# moth_v3_0.net
KiCad netlist of a schematic drawn in EAGLE
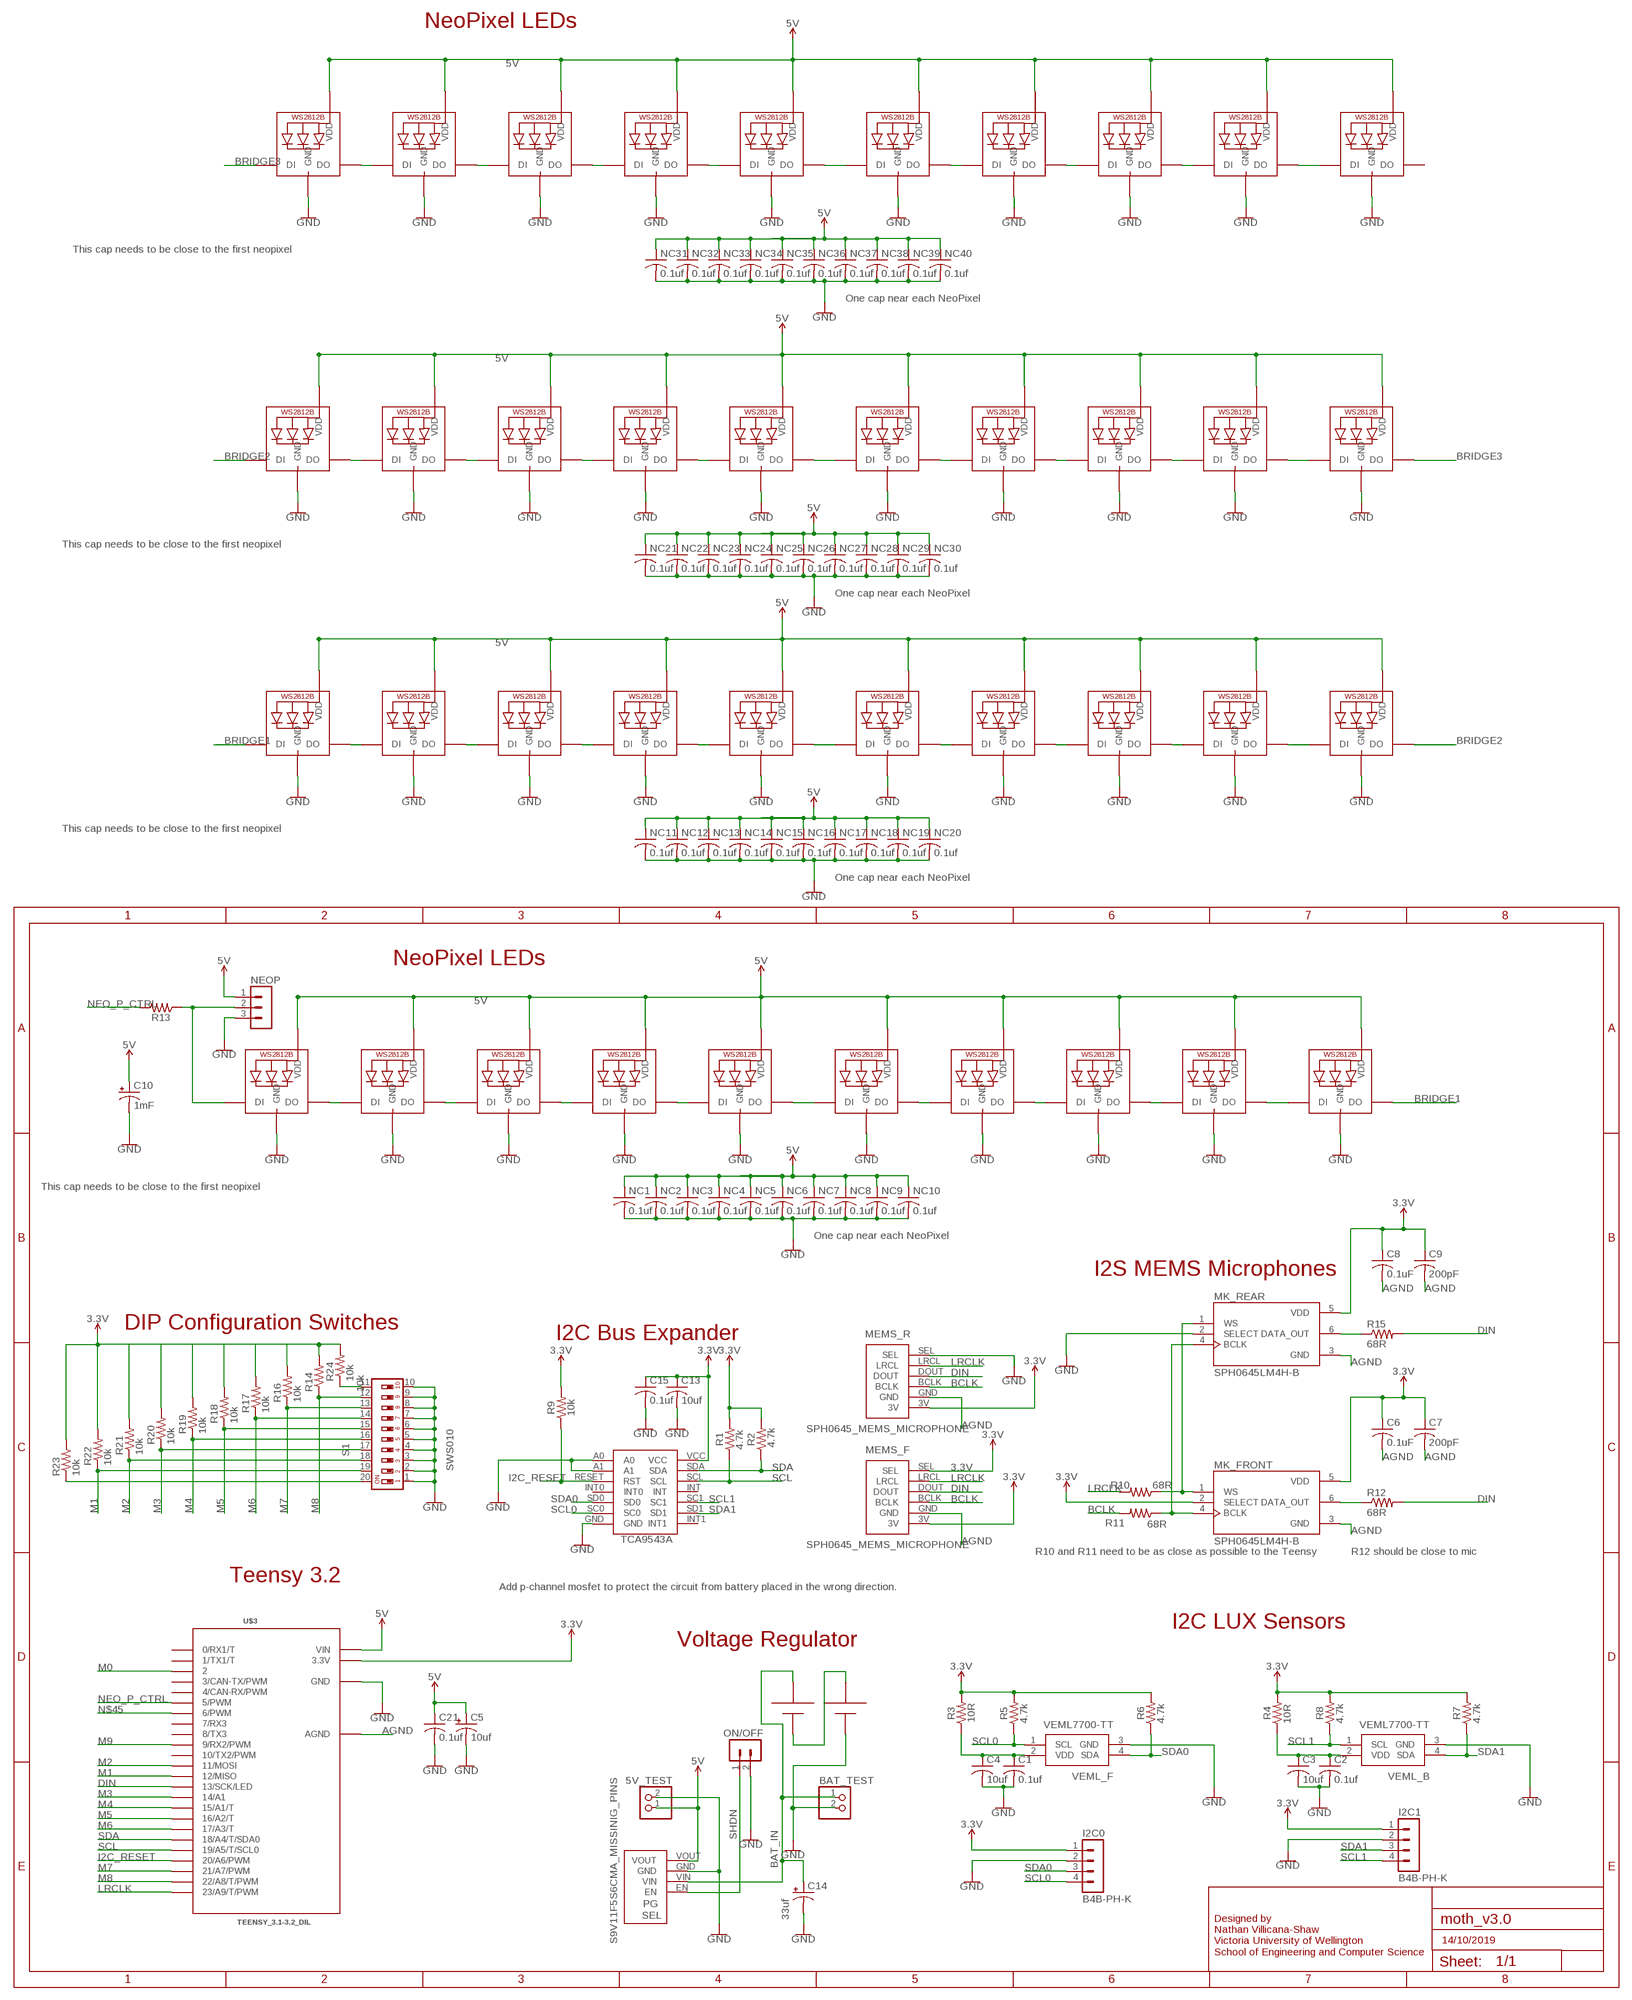
[diagram p0: schematic, sheet 1]

(export (version "E")
  (design (tool "Eeschema 10.0.6"))
  (components
    (comp (ref "5V_TEST")
      (value "PINHD-1X2")
      (footprint "eagle-import:1X02")
      (libsource (lib "eagle-import") (part "PINHD-1X2"))
    )
    (comp (ref "BAT_TEST")
      (value "PINHD-1X2")
      (footprint "eagle-import:1X02")
      (libsource (lib "eagle-import") (part "PINHD-1X2"))
    )
    (comp (ref "C1")
      (value "0.1uf")
      (footprint "eagle-import:C1206K")
      (libsource (lib "eagle-import") (part "C-USC1206K"))
    )
    (comp (ref "C2")
      (value "0.1uf")
      (footprint "eagle-import:C1206K")
      (libsource (lib "eagle-import") (part "C-USC1206K"))
    )
    (comp (ref "C3")
      (value "10uf")
      (footprint "eagle-import:C1206K")
      (libsource (lib "eagle-import") (part "C-USC1206K"))
    )
    (comp (ref "C4")
      (value "10uf")
      (footprint "eagle-import:C1206K")
      (libsource (lib "eagle-import") (part "C-USC1206K"))
    )
    (comp (ref "C5")
      (value "10uf")
      (footprint "eagle-import:E2,5-6")
      (libsource (lib "eagle-import") (part "CPOL-USE2.5-6"))
    )
    (comp (ref "C6")
      (value "0.1uF")
      (footprint "eagle-import:C1206K")
      (libsource (lib "eagle-import") (part "C-USC1206K"))
    )
    (comp (ref "C7")
      (value "200pF")
      (footprint "eagle-import:C1206K")
      (libsource (lib "eagle-import") (part "C-USC1206K"))
    )
    (comp (ref "C8")
      (value "0.1uF")
      (footprint "eagle-import:C1206K")
      (libsource (lib "eagle-import") (part "C-USC1206K"))
    )
    (comp (ref "C9")
      (value "200pF")
      (footprint "eagle-import:C1206K")
      (libsource (lib "eagle-import") (part "C-USC1206K"))
    )
    (comp (ref "C10")
      (value "1mF")
      (footprint "eagle-import:CPOL-RADIAL-5MM-10MM")
      (libsource (lib "eagle-import") (part "1000UF-RADIAL-5MM-25V-20%"))
    )
    (comp (ref "C13")
      (value "10uf")
      (footprint "eagle-import:C1206K")
      (libsource (lib "eagle-import") (part "C-USC1206K"))
    )
    (comp (ref "C14")
      (value "33uf")
      (footprint "eagle-import:E2-5")
      (libsource (lib "eagle-import") (part "CPOL-USE2-5"))
    )
    (comp (ref "C15")
      (value "0.1uf")
      (footprint "eagle-import:C1206K")
      (libsource (lib "eagle-import") (part "C-USC1206K"))
    )
    (comp (ref "C21")
      (value "0.1uf")
      (footprint "eagle-import:C1206K")
      (libsource (lib "eagle-import") (part "C-USC1206K"))
    )
    (comp (ref "I2C0")
      (value "B4B-PH-K")
      (footprint "eagle-import:B4B-PH-K")
      (libsource (lib "eagle-import") (part "B4B-PH-K"))
    )
    (comp (ref "I2C1")
      (value "B4B-PH-K")
      (footprint "eagle-import:B4B-PH-K")
      (libsource (lib "eagle-import") (part "B4B-PH-K"))
    )
    (comp (ref "MEMS_F")
      (value "SPH0645_MEMS_MICROPHONE")
      (footprint "eagle-import:SPH0645")
      (libsource (lib "eagle-import") (part "SPH0645_MEMS_MICROPHONE"))
    )
    (comp (ref "MEMS_R")
      (value "SPH0645_MEMS_MICROPHONE")
      (footprint "eagle-import:SPH0645")
      (libsource (lib "eagle-import") (part "SPH0645_MEMS_MICROPHONE"))
    )
    (comp (ref "MK_FRONT")
      (value "SPH0645LM4H-B")
      (footprint "eagle-import:MIC_SPH0645LM4H-B")
      (fields (field (name "DIGI-KEY_PART_NUMBER") "423-1405-1-ND") (field (name "MF") "Knowles"))
      (libsource (lib "eagle-import") (part "SPH0645LM4H-B"))
    )
    (comp (ref "MK_REAR")
      (value "SPH0645LM4H-B")
      (footprint "eagle-import:MIC_SPH0645LM4H-B")
      (fields (field (name "DIGI-KEY_PART_NUMBER") "423-1405-1-ND") (field (name "MF") "Knowles"))
      (libsource (lib "eagle-import") (part "SPH0645LM4H-B"))
    )
    (comp (ref "NC1")
      (value "0.1uf")
      (footprint "eagle-import:C1206K")
      (libsource (lib "eagle-import") (part "C-USC1206K"))
    )
    (comp (ref "NC2")
      (value "0.1uf")
      (footprint "eagle-import:C1206K")
      (libsource (lib "eagle-import") (part "C-USC1206K"))
    )
    (comp (ref "NC3")
      (value "0.1uf")
      (footprint "eagle-import:C1206K")
      (libsource (lib "eagle-import") (part "C-USC1206K"))
    )
    (comp (ref "NC4")
      (value "0.1uf")
      (footprint "eagle-import:C1206K")
      (libsource (lib "eagle-import") (part "C-USC1206K"))
    )
    (comp (ref "NC5")
      (value "0.1uf")
      (footprint "eagle-import:C1206K")
      (libsource (lib "eagle-import") (part "C-USC1206K"))
    )
    (comp (ref "NC6")
      (value "0.1uf")
      (footprint "eagle-import:C1206K")
      (libsource (lib "eagle-import") (part "C-USC1206K"))
    )
    (comp (ref "NC7")
      (value "0.1uf")
      (footprint "eagle-import:C1206K")
      (libsource (lib "eagle-import") (part "C-USC1206K"))
    )
    (comp (ref "NC8")
      (value "0.1uf")
      (footprint "eagle-import:C1206K")
      (libsource (lib "eagle-import") (part "C-USC1206K"))
    )
    (comp (ref "NC9")
      (value "0.1uf")
      (footprint "eagle-import:C1206K")
      (libsource (lib "eagle-import") (part "C-USC1206K"))
    )
    (comp (ref "NC10")
      (value "0.1uf")
      (footprint "eagle-import:C1206K")
      (libsource (lib "eagle-import") (part "C-USC1206K"))
    )
    (comp (ref "NC11")
      (value "0.1uf")
      (footprint "eagle-import:C1206K")
      (libsource (lib "eagle-import") (part "C-USC1206K"))
    )
    (comp (ref "NC12")
      (value "0.1uf")
      (footprint "eagle-import:C1206K")
      (libsource (lib "eagle-import") (part "C-USC1206K"))
    )
    (comp (ref "NC13")
      (value "0.1uf")
      (footprint "eagle-import:C1206K")
      (libsource (lib "eagle-import") (part "C-USC1206K"))
    )
    (comp (ref "NC14")
      (value "0.1uf")
      (footprint "eagle-import:C1206K")
      (libsource (lib "eagle-import") (part "C-USC1206K"))
    )
    (comp (ref "NC15")
      (value "0.1uf")
      (footprint "eagle-import:C1206K")
      (libsource (lib "eagle-import") (part "C-USC1206K"))
    )
    (comp (ref "NC16")
      (value "0.1uf")
      (footprint "eagle-import:C1206K")
      (libsource (lib "eagle-import") (part "C-USC1206K"))
    )
    (comp (ref "NC17")
      (value "0.1uf")
      (footprint "eagle-import:C1206K")
      (libsource (lib "eagle-import") (part "C-USC1206K"))
    )
    (comp (ref "NC18")
      (value "0.1uf")
      (footprint "eagle-import:C1206K")
      (libsource (lib "eagle-import") (part "C-USC1206K"))
    )
    (comp (ref "NC19")
      (value "0.1uf")
      (footprint "eagle-import:C1206K")
      (libsource (lib "eagle-import") (part "C-USC1206K"))
    )
    (comp (ref "NC20")
      (value "0.1uf")
      (footprint "eagle-import:C1206K")
      (libsource (lib "eagle-import") (part "C-USC1206K"))
    )
    (comp (ref "NC21")
      (value "0.1uf")
      (footprint "eagle-import:C1206K")
      (libsource (lib "eagle-import") (part "C-USC1206K"))
    )
    (comp (ref "NC22")
      (value "0.1uf")
      (footprint "eagle-import:C1206K")
      (libsource (lib "eagle-import") (part "C-USC1206K"))
    )
    (comp (ref "NC23")
      (value "0.1uf")
      (footprint "eagle-import:C1206K")
      (libsource (lib "eagle-import") (part "C-USC1206K"))
    )
    (comp (ref "NC24")
      (value "0.1uf")
      (footprint "eagle-import:C1206K")
      (libsource (lib "eagle-import") (part "C-USC1206K"))
    )
    (comp (ref "NC25")
      (value "0.1uf")
      (footprint "eagle-import:C1206K")
      (libsource (lib "eagle-import") (part "C-USC1206K"))
    )
    (comp (ref "NC26")
      (value "0.1uf")
      (footprint "eagle-import:C1206K")
      (libsource (lib "eagle-import") (part "C-USC1206K"))
    )
    (comp (ref "NC27")
      (value "0.1uf")
      (footprint "eagle-import:C1206K")
      (libsource (lib "eagle-import") (part "C-USC1206K"))
    )
    (comp (ref "NC28")
      (value "0.1uf")
      (footprint "eagle-import:C1206K")
      (libsource (lib "eagle-import") (part "C-USC1206K"))
    )
    (comp (ref "NC29")
      (value "0.1uf")
      (footprint "eagle-import:C1206K")
      (libsource (lib "eagle-import") (part "C-USC1206K"))
    )
    (comp (ref "NC30")
      (value "0.1uf")
      (footprint "eagle-import:C1206K")
      (libsource (lib "eagle-import") (part "C-USC1206K"))
    )
    (comp (ref "NC31")
      (value "0.1uf")
      (footprint "eagle-import:C1206K")
      (libsource (lib "eagle-import") (part "C-USC1206K"))
    )
    (comp (ref "NC32")
      (value "0.1uf")
      (footprint "eagle-import:C1206K")
      (libsource (lib "eagle-import") (part "C-USC1206K"))
    )
    (comp (ref "NC33")
      (value "0.1uf")
      (footprint "eagle-import:C1206K")
      (libsource (lib "eagle-import") (part "C-USC1206K"))
    )
    (comp (ref "NC34")
      (value "0.1uf")
      (footprint "eagle-import:C1206K")
      (libsource (lib "eagle-import") (part "C-USC1206K"))
    )
    (comp (ref "NC35")
      (value "0.1uf")
      (footprint "eagle-import:C1206K")
      (libsource (lib "eagle-import") (part "C-USC1206K"))
    )
    (comp (ref "NC36")
      (value "0.1uf")
      (footprint "eagle-import:C1206K")
      (libsource (lib "eagle-import") (part "C-USC1206K"))
    )
    (comp (ref "NC37")
      (value "0.1uf")
      (footprint "eagle-import:C1206K")
      (libsource (lib "eagle-import") (part "C-USC1206K"))
    )
    (comp (ref "NC38")
      (value "0.1uf")
      (footprint "eagle-import:C1206K")
      (libsource (lib "eagle-import") (part "C-USC1206K"))
    )
    (comp (ref "NC39")
      (value "0.1uf")
      (footprint "eagle-import:C1206K")
      (libsource (lib "eagle-import") (part "C-USC1206K"))
    )
    (comp (ref "NC40")
      (value "0.1uf")
      (footprint "eagle-import:C1206K")
      (libsource (lib "eagle-import") (part "C-USC1206K"))
    )
    (comp (ref "NEO1")
      (value "WS2812B5050")
      (footprint "eagle-import:WS2812B")
      (libsource (lib "eagle-import") (part "WS2812B5050"))
    )
    (comp (ref "NEO2")
      (value "WS2812B5050")
      (footprint "eagle-import:WS2812B")
      (libsource (lib "eagle-import") (part "WS2812B5050"))
    )
    (comp (ref "NEO3")
      (value "WS2812B5050")
      (footprint "eagle-import:WS2812B")
      (libsource (lib "eagle-import") (part "WS2812B5050"))
    )
    (comp (ref "NEO4")
      (value "WS2812B5050")
      (footprint "eagle-import:WS2812B")
      (libsource (lib "eagle-import") (part "WS2812B5050"))
    )
    (comp (ref "NEO5")
      (value "WS2812B5050")
      (footprint "eagle-import:WS2812B")
      (libsource (lib "eagle-import") (part "WS2812B5050"))
    )
    (comp (ref "NEO6")
      (value "WS2812B5050")
      (footprint "eagle-import:WS2812B")
      (libsource (lib "eagle-import") (part "WS2812B5050"))
    )
    (comp (ref "NEO7")
      (value "WS2812B5050")
      (footprint "eagle-import:WS2812B")
      (libsource (lib "eagle-import") (part "WS2812B5050"))
    )
    (comp (ref "NEO8")
      (value "WS2812B5050")
      (footprint "eagle-import:WS2812B")
      (libsource (lib "eagle-import") (part "WS2812B5050"))
    )
    (comp (ref "NEO9")
      (value "WS2812B5050")
      (footprint "eagle-import:WS2812B")
      (libsource (lib "eagle-import") (part "WS2812B5050"))
    )
    (comp (ref "NEO10")
      (value "WS2812B5050")
      (footprint "eagle-import:WS2812B")
      (libsource (lib "eagle-import") (part "WS2812B5050"))
    )
    (comp (ref "NEO11")
      (value "WS2812B5050")
      (footprint "eagle-import:WS2812B")
      (libsource (lib "eagle-import") (part "WS2812B5050"))
    )
    (comp (ref "NEO12")
      (value "WS2812B5050")
      (footprint "eagle-import:WS2812B")
      (libsource (lib "eagle-import") (part "WS2812B5050"))
    )
    (comp (ref "NEO13")
      (value "WS2812B5050")
      (footprint "eagle-import:WS2812B")
      (libsource (lib "eagle-import") (part "WS2812B5050"))
    )
    (comp (ref "NEO14")
      (value "WS2812B5050")
      (footprint "eagle-import:WS2812B")
      (libsource (lib "eagle-import") (part "WS2812B5050"))
    )
    (comp (ref "NEO15")
      (value "WS2812B5050")
      (footprint "eagle-import:WS2812B")
      (libsource (lib "eagle-import") (part "WS2812B5050"))
    )
    (comp (ref "NEO16")
      (value "WS2812B5050")
      (footprint "eagle-import:WS2812B")
      (libsource (lib "eagle-import") (part "WS2812B5050"))
    )
    (comp (ref "NEO17")
      (value "WS2812B5050")
      (footprint "eagle-import:WS2812B")
      (libsource (lib "eagle-import") (part "WS2812B5050"))
    )
    (comp (ref "NEO18")
      (value "WS2812B5050")
      (footprint "eagle-import:WS2812B")
      (libsource (lib "eagle-import") (part "WS2812B5050"))
    )
    (comp (ref "NEO19")
      (value "WS2812B5050")
      (footprint "eagle-import:WS2812B")
      (libsource (lib "eagle-import") (part "WS2812B5050"))
    )
    (comp (ref "NEO20")
      (value "WS2812B5050")
      (footprint "eagle-import:WS2812B")
      (libsource (lib "eagle-import") (part "WS2812B5050"))
    )
    (comp (ref "NEO21")
      (value "WS2812B5050")
      (footprint "eagle-import:WS2812B")
      (libsource (lib "eagle-import") (part "WS2812B5050"))
    )
    (comp (ref "NEO22")
      (value "WS2812B5050")
      (footprint "eagle-import:WS2812B")
      (libsource (lib "eagle-import") (part "WS2812B5050"))
    )
    (comp (ref "NEO23")
      (value "WS2812B5050")
      (footprint "eagle-import:WS2812B")
      (libsource (lib "eagle-import") (part "WS2812B5050"))
    )
    (comp (ref "NEO24")
      (value "WS2812B5050")
      (footprint "eagle-import:WS2812B")
      (libsource (lib "eagle-import") (part "WS2812B5050"))
    )
    (comp (ref "NEO25")
      (value "WS2812B5050")
      (footprint "eagle-import:WS2812B")
      (libsource (lib "eagle-import") (part "WS2812B5050"))
    )
    (comp (ref "NEO26")
      (value "WS2812B5050")
      (footprint "eagle-import:WS2812B")
      (libsource (lib "eagle-import") (part "WS2812B5050"))
    )
    (comp (ref "NEO27")
      (value "WS2812B5050")
      (footprint "eagle-import:WS2812B")
      (libsource (lib "eagle-import") (part "WS2812B5050"))
    )
    (comp (ref "NEO28")
      (value "WS2812B5050")
      (footprint "eagle-import:WS2812B")
      (libsource (lib "eagle-import") (part "WS2812B5050"))
    )
    (comp (ref "NEO29")
      (value "WS2812B5050")
      (footprint "eagle-import:WS2812B")
      (libsource (lib "eagle-import") (part "WS2812B5050"))
    )
    (comp (ref "NEO30")
      (value "WS2812B5050")
      (footprint "eagle-import:WS2812B")
      (libsource (lib "eagle-import") (part "WS2812B5050"))
    )
    (comp (ref "NEO31")
      (value "WS2812B5050")
      (footprint "eagle-import:WS2812B")
      (libsource (lib "eagle-import") (part "WS2812B5050"))
    )
    (comp (ref "NEO32")
      (value "WS2812B5050")
      (footprint "eagle-import:WS2812B")
      (libsource (lib "eagle-import") (part "WS2812B5050"))
    )
    (comp (ref "NEO33")
      (value "WS2812B5050")
      (footprint "eagle-import:WS2812B")
      (libsource (lib "eagle-import") (part "WS2812B5050"))
    )
    (comp (ref "NEO34")
      (value "WS2812B5050")
      (footprint "eagle-import:WS2812B")
      (libsource (lib "eagle-import") (part "WS2812B5050"))
    )
    (comp (ref "NEO35")
      (value "WS2812B5050")
      (footprint "eagle-import:WS2812B")
      (libsource (lib "eagle-import") (part "WS2812B5050"))
    )
    (comp (ref "NEO36")
      (value "WS2812B5050")
      (footprint "eagle-import:WS2812B")
      (libsource (lib "eagle-import") (part "WS2812B5050"))
    )
    (comp (ref "NEO37")
      (value "WS2812B5050")
      (footprint "eagle-import:WS2812B")
      (libsource (lib "eagle-import") (part "WS2812B5050"))
    )
    (comp (ref "NEO38")
      (value "WS2812B5050")
      (footprint "eagle-import:WS2812B")
      (libsource (lib "eagle-import") (part "WS2812B5050"))
    )
    (comp (ref "NEO39")
      (value "WS2812B5050")
      (footprint "eagle-import:WS2812B")
      (libsource (lib "eagle-import") (part "WS2812B5050"))
    )
    (comp (ref "NEO40")
      (value "WS2812B5050")
      (footprint "eagle-import:WS2812B")
      (libsource (lib "eagle-import") (part "WS2812B5050"))
    )
    (comp (ref "NEOP")
      (value "B3B-PH-K")
      (footprint "eagle-import:B3B-PH-K")
      (libsource (lib "eagle-import") (part "B3B-PH-K"))
    )
    (comp (ref "ON/OFF")
      (value "B2B-PH-K")
      (footprint "eagle-import:B2B-PH-K")
      (libsource (lib "eagle-import") (part "B2B-PH-K"))
    )
    (comp (ref "R1")
      (value "4.7k")
      (footprint "eagle-import:R1206W")
      (libsource (lib "eagle-import") (part "R-US_R1206W"))
    )
    (comp (ref "R2")
      (value "4.7k")
      (footprint "eagle-import:R1206W")
      (libsource (lib "eagle-import") (part "R-US_R1206W"))
    )
    (comp (ref "R3")
      (value "10R")
      (footprint "eagle-import:R1206W")
      (libsource (lib "eagle-import") (part "R-US_R1206W"))
    )
    (comp (ref "R4")
      (value "10R")
      (footprint "eagle-import:R1206W")
      (libsource (lib "eagle-import") (part "R-US_R1206W"))
    )
    (comp (ref "R5")
      (value "4.7k")
      (footprint "eagle-import:R1206W")
      (libsource (lib "eagle-import") (part "R-US_R1206W"))
    )
    (comp (ref "R6")
      (value "4.7k")
      (footprint "eagle-import:R1206W")
      (libsource (lib "eagle-import") (part "R-US_R1206W"))
    )
    (comp (ref "R7")
      (value "4.7k")
      (footprint "eagle-import:R1206W")
      (libsource (lib "eagle-import") (part "R-US_R1206W"))
    )
    (comp (ref "R8")
      (value "4.7k")
      (footprint "eagle-import:R1206W")
      (libsource (lib "eagle-import") (part "R-US_R1206W"))
    )
    (comp (ref "R9")
      (value "10k")
      (footprint "eagle-import:R1206W")
      (libsource (lib "eagle-import") (part "R-US_R1206W"))
    )
    (comp (ref "R10")
      (value "68R")
      (footprint "eagle-import:M1206")
      (libsource (lib "eagle-import") (part "R-US_M1206"))
    )
    (comp (ref "R11")
      (value "68R")
      (footprint "eagle-import:M1206")
      (libsource (lib "eagle-import") (part "R-US_M1206"))
    )
    (comp (ref "R12")
      (value "68R")
      (footprint "eagle-import:M1206")
      (libsource (lib "eagle-import") (part "R-US_M1206"))
    )
    (comp (ref "R13")
      (value "300 R")
      (footprint "eagle-import:R1206W")
      (libsource (lib "eagle-import") (part "R-US_R1206W"))
    )
    (comp (ref "R14")
      (value "10k")
      (footprint "eagle-import:R1206W")
      (libsource (lib "eagle-import") (part "R-US_R1206W"))
    )
    (comp (ref "R15")
      (value "68R")
      (footprint "eagle-import:M1206")
      (libsource (lib "eagle-import") (part "R-US_M1206"))
    )
    (comp (ref "R16")
      (value "10k")
      (footprint "eagle-import:R1206W")
      (libsource (lib "eagle-import") (part "R-US_R1206W"))
    )
    (comp (ref "R17")
      (value "10k")
      (footprint "eagle-import:R1206W")
      (libsource (lib "eagle-import") (part "R-US_R1206W"))
    )
    (comp (ref "R18")
      (value "10k")
      (footprint "eagle-import:R1206W")
      (libsource (lib "eagle-import") (part "R-US_R1206W"))
    )
    (comp (ref "R19")
      (value "10k")
      (footprint "eagle-import:R1206W")
      (libsource (lib "eagle-import") (part "R-US_R1206W"))
    )
    (comp (ref "R20")
      (value "10k")
      (footprint "eagle-import:R1206W")
      (libsource (lib "eagle-import") (part "R-US_R1206W"))
    )
    (comp (ref "R21")
      (value "10k")
      (footprint "eagle-import:R1206W")
      (libsource (lib "eagle-import") (part "R-US_R1206W"))
    )
    (comp (ref "R22")
      (value "10k")
      (footprint "eagle-import:R1206W")
      (libsource (lib "eagle-import") (part "R-US_R1206W"))
    )
    (comp (ref "R23")
      (value "10k")
      (footprint "eagle-import:R1206W")
      (libsource (lib "eagle-import") (part "R-US_R1206W"))
    )
    (comp (ref "R24")
      (value "10k")
      (footprint "eagle-import:R1206W")
      (libsource (lib "eagle-import") (part "R-US_R1206W"))
    )
    (comp (ref "S1")
      (value "SWS010")
      (footprint "eagle-import:SMS-010")
      (libsource (lib "eagle-import") (part "SWS010"))
    )
    (comp (ref "U$1")
      (value "TCA9543A")
      (footprint "eagle-import:SO14")
      (libsource (lib "eagle-import") (part "TCA9543A"))
    )
    (comp (ref "U$2")
      (value "BK-18650-PC4")
      (footprint "eagle-import:18650-PC4")
      (fields (field (name "MF") "MPD"))
      (libsource (lib "eagle-import") (part "BK-18650-PC4"))
    )
    (comp (ref "U$3")
      (value "TEENSY_3.1-3.2_DIL")
      (footprint "eagle-import:TEENSY_3.0-3.2&LC_DIL")
      (libsource (lib "eagle-import") (part "TEENSY_3.1-3.2_DIL"))
    )
    (comp (ref "U$6")
      (value "S9V11F5S6CMA_MISSINIG_PINS")
      (footprint "eagle-import:S9V11F3S5CMA_MISSING_PINS")
      (libsource (lib "eagle-import") (part "S9V11F5S6CMA_MISSINIG_PINS"))
    )
    (comp (ref "VEML_B")
      (value "VEML7700-TT")
      (footprint "eagle-import:VEML7700")
      (fields (field (name "MOUSER_PART_NUMBER") "78-VEML7700-TT") (field (name "RS_PART_NUMBER") "1226791P"))
      (libsource (lib "eagle-import") (part "VEML7700-TT"))
    )
    (comp (ref "VEML_F")
      (value "VEML7700-TT")
      (footprint "eagle-import:VEML7700")
      (fields (field (name "MOUSER_PART_NUMBER") "78-VEML7700-TT") (field (name "RS_PART_NUMBER") "1226791P"))
      (libsource (lib "eagle-import") (part "VEML7700-TT"))
    )
  )
  (nets
    (net (code "1") (name "/AGND") (class "Default")
      (node (ref "C6") (pin "2") (pinfunction "2_2") (pintype "passive"))
      (node (ref "C7") (pin "2") (pinfunction "2_2") (pintype "passive"))
      (node (ref "C8") (pin "2") (pinfunction "2_2") (pintype "passive"))
      (node (ref "C9") (pin "2") (pinfunction "2_2") (pintype "passive"))
      (node (ref "MEMS_F") (pin "GND") (pinfunction "GND_GND") (pintype "bidirectional"))
      (node (ref "MEMS_R") (pin "GND") (pinfunction "GND_GND") (pintype "bidirectional"))
      (node (ref "MK_FRONT") (pin "3") (pinfunction "GND_3") (pintype "power_in"))
      (node (ref "MK_REAR") (pin "3") (pinfunction "GND_3") (pintype "power_in"))
      (node (ref "U$3") (pin "AGND") (pinfunction "AGND_AGND") (pintype "power_in"))
    )
    (net (code "2") (name "/BAT_IN") (class "Default")
      (node (ref "BAT_TEST") (pin "1") (pinfunction "1_1") (pintype "passive"))
      (node (ref "C14") (pin "+") (pinfunction "+_+") (pintype "passive"))
      (node (ref "U$2") (pin "+1") (pinfunction "+1_+1") (pintype "bidirectional"))
      (node (ref "U$6") (pin "VIN") (pinfunction "VIN_VIN") (pintype "bidirectional"))
    )
    (net (code "3") (name "/BCLK") (class "Default")
      (node (ref "MEMS_F") (pin "BCLK") (pinfunction "BCLK_BCLK") (pintype "bidirectional"))
      (node (ref "MEMS_R") (pin "BCLK") (pinfunction "BCLK_BCLK") (pintype "bidirectional"))
      (node (ref "R11") (pin "2") (pinfunction "2_2") (pintype "passive"))
    )
    (net (code "4") (name "/BRIDGE1") (class "Default")
      (node (ref "NEO10") (pin "2-DOUT") (pinfunction "DO_2-DOUT") (pintype "output"))
      (node (ref "NEO14") (pin "4-DIN") (pinfunction "DI_4-DIN") (pintype "input"))
    )
    (net (code "5") (name "/BRIDGE2") (class "Default")
      (node (ref "NEO20") (pin "2-DOUT") (pinfunction "DO_2-DOUT") (pintype "output"))
      (node (ref "NEO24") (pin "4-DIN") (pinfunction "DI_4-DIN") (pintype "input"))
    )
    (net (code "6") (name "/BRIDGE3") (class "Default")
      (node (ref "NEO30") (pin "2-DOUT") (pinfunction "DO_2-DOUT") (pintype "output"))
      (node (ref "NEO34") (pin "4-DIN") (pinfunction "DI_4-DIN") (pintype "input"))
    )
    (net (code "7") (name "/DIN") (class "Default")
      (node (ref "MEMS_F") (pin "DOUT") (pinfunction "DOUT_DOUT") (pintype "bidirectional"))
      (node (ref "MEMS_R") (pin "DOUT") (pinfunction "DOUT_DOUT") (pintype "bidirectional"))
      (node (ref "R12") (pin "2") (pinfunction "2_2") (pintype "passive"))
      (node (ref "R15") (pin "2") (pinfunction "2_2") (pintype "passive"))
      (node (ref "U$3") (pin "13") (pinfunction "13/SCK/LED_13") (pintype "bidirectional"))
    )
    (net (code "8") (name "/I2C_RESET") (class "Default")
      (node (ref "R9") (pin "1") (pinfunction "1_1") (pintype "passive"))
      (node (ref "U$1") (pin "RESET") (pinfunction "RST_RESET") (pintype "bidirectional"))
      (node (ref "U$3") (pin "20/A6") (pinfunction "20/A6/PWM_20/A6") (pintype "bidirectional"))
    )
    (net (code "9") (name "/LRCLK") (class "Default")
      (node (ref "MEMS_F") (pin "LRCL") (pinfunction "LRCL_LRCL") (pintype "bidirectional"))
      (node (ref "MEMS_R") (pin "LRCL") (pinfunction "LRCL_LRCL") (pintype "bidirectional"))
      (node (ref "R10") (pin "2") (pinfunction "2_2") (pintype "passive"))
      (node (ref "U$3") (pin "23/A9") (pinfunction "23/A9/T/PWM_23/A9") (pintype "bidirectional"))
    )
    (net (code "10") (name "/M0") (class "Default")
      (node (ref "U$3") (pin "2") (pinfunction "2_2") (pintype "bidirectional"))
    )
    (net (code "11") (name "/M1") (class "Default")
      (node (ref "R22") (pin "1") (pinfunction "1_1") (pintype "passive"))
      (node (ref "S1") (pin "19") (pinfunction "19_19") (pintype "passive"))
      (node (ref "U$3") (pin "12") (pinfunction "12/MISO_12") (pintype "bidirectional"))
    )
    (net (code "12") (name "/M2") (class "Default")
      (node (ref "R21") (pin "1") (pinfunction "1_1") (pintype "passive"))
      (node (ref "S1") (pin "18") (pinfunction "18_18") (pintype "passive"))
      (node (ref "U$3") (pin "11") (pinfunction "11/MOSI_11") (pintype "bidirectional"))
    )
    (net (code "13") (name "/M3") (class "Default")
      (node (ref "R20") (pin "1") (pinfunction "1_1") (pintype "passive"))
      (node (ref "S1") (pin "17") (pinfunction "17_17") (pintype "passive"))
      (node (ref "U$3") (pin "14/A0") (pinfunction "14/A1_14/A0") (pintype "bidirectional"))
    )
    (net (code "14") (name "/M4") (class "Default")
      (node (ref "R19") (pin "1") (pinfunction "1_1") (pintype "passive"))
      (node (ref "S1") (pin "16") (pinfunction "16_16") (pintype "passive"))
      (node (ref "U$3") (pin "15/A1") (pinfunction "15/A1/T_15/A1") (pintype "bidirectional"))
    )
    (net (code "15") (name "/M5") (class "Default")
      (node (ref "R18") (pin "1") (pinfunction "1_1") (pintype "passive"))
      (node (ref "S1") (pin "15") (pinfunction "15_15") (pintype "passive"))
      (node (ref "U$3") (pin "16/A2") (pinfunction "16/A2/T_16/A2") (pintype "bidirectional"))
    )
    (net (code "16") (name "/M6") (class "Default")
      (node (ref "R17") (pin "1") (pinfunction "1_1") (pintype "passive"))
      (node (ref "S1") (pin "14") (pinfunction "14_14") (pintype "passive"))
      (node (ref "U$3") (pin "17/A3") (pinfunction "17/A3/T_17/A3") (pintype "bidirectional"))
    )
    (net (code "17") (name "/M7") (class "Default")
      (node (ref "R16") (pin "1") (pinfunction "1_1") (pintype "passive"))
      (node (ref "S1") (pin "13") (pinfunction "13_13") (pintype "passive"))
      (node (ref "U$3") (pin "21/A7") (pinfunction "21/A7/PWM_21/A7") (pintype "bidirectional"))
    )
    (net (code "18") (name "/M8") (class "Default")
      (node (ref "R14") (pin "1") (pinfunction "1_1") (pintype "passive"))
      (node (ref "S1") (pin "12") (pinfunction "12_12") (pintype "passive"))
      (node (ref "U$3") (pin "22/A8") (pinfunction "22/A8/T/PWM_22/A8") (pintype "bidirectional"))
    )
    (net (code "19") (name "/M9") (class "Default")
      (node (ref "U$3") (pin "9") (pinfunction "9/RX2/PWM_9") (pintype "bidirectional"))
    )
    (net (code "20") (name "/N$45") (class "Default")
      (node (ref "U$3") (pin "6") (pinfunction "6/PWM_6") (pintype "bidirectional"))
    )
    (net (code "21") (name "/NEO_P_CTRL") (class "Default")
      (node (ref "R13") (pin "2") (pinfunction "2_2") (pintype "passive"))
      (node (ref "U$3") (pin "5") (pinfunction "5/PWM_5") (pintype "bidirectional"))
    )
    (net (code "22") (name "/SCL") (class "Default")
      (node (ref "R1") (pin "1") (pinfunction "1_1") (pintype "passive"))
      (node (ref "U$1") (pin "SCL") (pinfunction "SCL_SCL") (pintype "bidirectional"))
      (node (ref "U$3") (pin "19/A5") (pinfunction "19/A5/T/SCL0_19/A5") (pintype "bidirectional"))
    )
    (net (code "23") (name "/SCL0") (class "Default")
      (node (ref "I2C0") (pin "4") (pinfunction "4_4") (pintype "passive"))
      (node (ref "R5") (pin "1") (pinfunction "1_1") (pintype "passive"))
      (node (ref "U$1") (pin "SC0") (pinfunction "SC0_SC0") (pintype "bidirectional"))
      (node (ref "VEML_F") (pin "1") (pinfunction "SCL_1") (pintype "bidirectional"))
    )
    (net (code "24") (name "/SCL1") (class "Default")
      (node (ref "I2C1") (pin "4") (pinfunction "4_4") (pintype "passive"))
      (node (ref "R8") (pin "1") (pinfunction "1_1") (pintype "passive"))
      (node (ref "U$1") (pin "SC1") (pinfunction "SC1_SC1") (pintype "bidirectional"))
      (node (ref "VEML_B") (pin "1") (pinfunction "SCL_1") (pintype "bidirectional"))
    )
    (net (code "25") (name "/SDA") (class "Default")
      (node (ref "R2") (pin "1") (pinfunction "1_1") (pintype "passive"))
      (node (ref "U$1") (pin "SDA") (pinfunction "SDA_SDA") (pintype "bidirectional"))
      (node (ref "U$3") (pin "18/A4") (pinfunction "18/A4/T/SDA0_18/A4") (pintype "bidirectional"))
    )
    (net (code "26") (name "/SDA0") (class "Default")
      (node (ref "I2C0") (pin "3") (pinfunction "3_3") (pintype "passive"))
      (node (ref "R6") (pin "1") (pinfunction "1_1") (pintype "passive"))
      (node (ref "U$1") (pin "SD0") (pinfunction "SD0_SD0") (pintype "bidirectional"))
      (node (ref "VEML_F") (pin "4") (pinfunction "SDA_4") (pintype "bidirectional"))
    )
    (net (code "27") (name "/SDA1") (class "Default")
      (node (ref "I2C1") (pin "3") (pinfunction "3_3") (pintype "passive"))
      (node (ref "R7") (pin "1") (pinfunction "1_1") (pintype "passive"))
      (node (ref "U$1") (pin "SD1") (pinfunction "SD1_SD1") (pintype "bidirectional"))
      (node (ref "VEML_B") (pin "4") (pinfunction "SDA_4") (pintype "bidirectional"))
    )
    (net (code "28") (name "/SHDN") (class "Default")
      (node (ref "ON/OFF") (pin "1") (pinfunction "1_1") (pintype "passive"))
      (node (ref "U$6") (pin "EN") (pinfunction "EN_EN") (pintype "bidirectional"))
    )
    (net (code "29") (name "3.3V") (class "Default")
      (node (ref "C13") (pin "1") (pinfunction "1_1") (pintype "passive"))
      (node (ref "C15") (pin "1") (pinfunction "1_1") (pintype "passive"))
      (node (ref "C6") (pin "1") (pinfunction "1_1") (pintype "passive"))
      (node (ref "C7") (pin "1") (pinfunction "1_1") (pintype "passive"))
      (node (ref "C8") (pin "1") (pinfunction "1_1") (pintype "passive"))
      (node (ref "C9") (pin "1") (pinfunction "1_1") (pintype "passive"))
      (node (ref "I2C0") (pin "1") (pinfunction "1_1") (pintype "passive"))
      (node (ref "I2C1") (pin "1") (pinfunction "1_1") (pintype "passive"))
      (node (ref "MEMS_F") (pin "3V") (pinfunction "3V_3V") (pintype "bidirectional"))
      (node (ref "MEMS_F") (pin "SEL") (pinfunction "SEL_SEL") (pintype "bidirectional"))
      (node (ref "MEMS_R") (pin "3V") (pinfunction "3V_3V") (pintype "bidirectional"))
      (node (ref "MK_FRONT") (pin "2") (pinfunction "SELECT_2") (pintype "input"))
      (node (ref "MK_FRONT") (pin "5") (pinfunction "VDD_5") (pintype "power_in"))
      (node (ref "MK_REAR") (pin "5") (pinfunction "VDD_5") (pintype "power_in"))
      (node (ref "R1") (pin "2") (pinfunction "2_2") (pintype "passive"))
      (node (ref "R14") (pin "2") (pinfunction "2_2") (pintype "passive"))
      (node (ref "R2") (pin "2") (pinfunction "2_2") (pintype "passive"))
      (node (ref "R22") (pin "2") (pinfunction "2_2") (pintype "passive"))
      (node (ref "R23") (pin "2") (pinfunction "2_2") (pintype "passive"))
      (node (ref "R24") (pin "2") (pinfunction "2_2") (pintype "passive"))
      (node (ref "R3") (pin "2") (pinfunction "2_2") (pintype "passive"))
      (node (ref "R4") (pin "2") (pinfunction "2_2") (pintype "passive"))
      (node (ref "R5") (pin "2") (pinfunction "2_2") (pintype "passive"))
      (node (ref "R6") (pin "2") (pinfunction "2_2") (pintype "passive"))
      (node (ref "R7") (pin "2") (pinfunction "2_2") (pintype "passive"))
      (node (ref "R8") (pin "2") (pinfunction "2_2") (pintype "passive"))
      (node (ref "R9") (pin "2") (pinfunction "2_2") (pintype "passive"))
      (node (ref "U$1") (pin "VCC") (pinfunction "VCC_VCC") (pintype "bidirectional"))
      (node (ref "U$3") (pin "3.3V") (pinfunction "3.3V_3.3V") (pintype "power_in"))
    )
    (net (code "30") (name "5V") (class "Default")
      (node (ref "5V_TEST") (pin "1") (pinfunction "1_1") (pintype "passive"))
      (node (ref "C10") (pin "+") (pinfunction "+_+") (pintype "passive"))
      (node (ref "C21") (pin "1") (pinfunction "1_1") (pintype "passive"))
      (node (ref "C5") (pin "+") (pinfunction "+_+") (pintype "passive"))
      (node (ref "NC1") (pin "1") (pinfunction "1_1") (pintype "passive"))
      (node (ref "NC10") (pin "1") (pinfunction "1_1") (pintype "passive"))
      (node (ref "NC11") (pin "1") (pinfunction "1_1") (pintype "passive"))
      (node (ref "NC12") (pin "1") (pinfunction "1_1") (pintype "passive"))
      (node (ref "NC13") (pin "1") (pinfunction "1_1") (pintype "passive"))
      (node (ref "NC14") (pin "1") (pinfunction "1_1") (pintype "passive"))
      (node (ref "NC15") (pin "1") (pinfunction "1_1") (pintype "passive"))
      (node (ref "NC16") (pin "1") (pinfunction "1_1") (pintype "passive"))
      (node (ref "NC17") (pin "1") (pinfunction "1_1") (pintype "passive"))
      (node (ref "NC18") (pin "1") (pinfunction "1_1") (pintype "passive"))
      (node (ref "NC19") (pin "1") (pinfunction "1_1") (pintype "passive"))
      (node (ref "NC2") (pin "1") (pinfunction "1_1") (pintype "passive"))
      (node (ref "NC20") (pin "1") (pinfunction "1_1") (pintype "passive"))
      (node (ref "NC21") (pin "1") (pinfunction "1_1") (pintype "passive"))
      (node (ref "NC22") (pin "1") (pinfunction "1_1") (pintype "passive"))
      (node (ref "NC23") (pin "1") (pinfunction "1_1") (pintype "passive"))
      (node (ref "NC24") (pin "1") (pinfunction "1_1") (pintype "passive"))
      (node (ref "NC25") (pin "1") (pinfunction "1_1") (pintype "passive"))
      (node (ref "NC26") (pin "1") (pinfunction "1_1") (pintype "passive"))
      (node (ref "NC27") (pin "1") (pinfunction "1_1") (pintype "passive"))
      (node (ref "NC28") (pin "1") (pinfunction "1_1") (pintype "passive"))
      (node (ref "NC29") (pin "1") (pinfunction "1_1") (pintype "passive"))
      (node (ref "NC3") (pin "1") (pinfunction "1_1") (pintype "passive"))
      (node (ref "NC30") (pin "1") (pinfunction "1_1") (pintype "passive"))
      (node (ref "NC31") (pin "1") (pinfunction "1_1") (pintype "passive"))
      (node (ref "NC32") (pin "1") (pinfunction "1_1") (pintype "passive"))
      (node (ref "NC33") (pin "1") (pinfunction "1_1") (pintype "passive"))
      (node (ref "NC34") (pin "1") (pinfunction "1_1") (pintype "passive"))
      (node (ref "NC35") (pin "1") (pinfunction "1_1") (pintype "passive"))
      (node (ref "NC36") (pin "1") (pinfunction "1_1") (pintype "passive"))
      (node (ref "NC37") (pin "1") (pinfunction "1_1") (pintype "passive"))
      (node (ref "NC38") (pin "1") (pinfunction "1_1") (pintype "passive"))
      (node (ref "NC39") (pin "1") (pinfunction "1_1") (pintype "passive"))
      (node (ref "NC4") (pin "1") (pinfunction "1_1") (pintype "passive"))
      (node (ref "NC40") (pin "1") (pinfunction "1_1") (pintype "passive"))
      (node (ref "NC5") (pin "1") (pinfunction "1_1") (pintype "passive"))
      (node (ref "NC6") (pin "1") (pinfunction "1_1") (pintype "passive"))
      (node (ref "NC7") (pin "1") (pinfunction "1_1") (pintype "passive"))
      (node (ref "NC8") (pin "1") (pinfunction "1_1") (pintype "passive"))
      (node (ref "NC9") (pin "1") (pinfunction "1_1") (pintype "passive"))
      (node (ref "NEO1") (pin "1-VDD") (pinfunction "VDD_1-VDD") (pintype "power_in"))
      (node (ref "NEO10") (pin "1-VDD") (pinfunction "VDD_1-VDD") (pintype "power_in"))
      (node (ref "NEO11") (pin "1-VDD") (pinfunction "VDD_1-VDD") (pintype "power_in"))
      (node (ref "NEO12") (pin "1-VDD") (pinfunction "VDD_1-VDD") (pintype "power_in"))
      (node (ref "NEO13") (pin "1-VDD") (pinfunction "VDD_1-VDD") (pintype "power_in"))
      (node (ref "NEO14") (pin "1-VDD") (pinfunction "VDD_1-VDD") (pintype "power_in"))
      (node (ref "NEO15") (pin "1-VDD") (pinfunction "VDD_1-VDD") (pintype "power_in"))
      (node (ref "NEO16") (pin "1-VDD") (pinfunction "VDD_1-VDD") (pintype "power_in"))
      (node (ref "NEO17") (pin "1-VDD") (pinfunction "VDD_1-VDD") (pintype "power_in"))
      (node (ref "NEO18") (pin "1-VDD") (pinfunction "VDD_1-VDD") (pintype "power_in"))
      (node (ref "NEO19") (pin "1-VDD") (pinfunction "VDD_1-VDD") (pintype "power_in"))
      (node (ref "NEO2") (pin "1-VDD") (pinfunction "VDD_1-VDD") (pintype "power_in"))
      (node (ref "NEO20") (pin "1-VDD") (pinfunction "VDD_1-VDD") (pintype "power_in"))
      (node (ref "NEO21") (pin "1-VDD") (pinfunction "VDD_1-VDD") (pintype "power_in"))
      (node (ref "NEO22") (pin "1-VDD") (pinfunction "VDD_1-VDD") (pintype "power_in"))
      (node (ref "NEO23") (pin "1-VDD") (pinfunction "VDD_1-VDD") (pintype "power_in"))
      (node (ref "NEO24") (pin "1-VDD") (pinfunction "VDD_1-VDD") (pintype "power_in"))
      (node (ref "NEO25") (pin "1-VDD") (pinfunction "VDD_1-VDD") (pintype "power_in"))
      (node (ref "NEO26") (pin "1-VDD") (pinfunction "VDD_1-VDD") (pintype "power_in"))
      (node (ref "NEO27") (pin "1-VDD") (pinfunction "VDD_1-VDD") (pintype "power_in"))
      (node (ref "NEO28") (pin "1-VDD") (pinfunction "VDD_1-VDD") (pintype "power_in"))
      (node (ref "NEO29") (pin "1-VDD") (pinfunction "VDD_1-VDD") (pintype "power_in"))
      (node (ref "NEO3") (pin "1-VDD") (pinfunction "VDD_1-VDD") (pintype "power_in"))
      (node (ref "NEO30") (pin "1-VDD") (pinfunction "VDD_1-VDD") (pintype "power_in"))
      (node (ref "NEO31") (pin "1-VDD") (pinfunction "VDD_1-VDD") (pintype "power_in"))
      (node (ref "NEO32") (pin "1-VDD") (pinfunction "VDD_1-VDD") (pintype "power_in"))
      (node (ref "NEO33") (pin "1-VDD") (pinfunction "VDD_1-VDD") (pintype "power_in"))
      (node (ref "NEO34") (pin "1-VDD") (pinfunction "VDD_1-VDD") (pintype "power_in"))
      (node (ref "NEO35") (pin "1-VDD") (pinfunction "VDD_1-VDD") (pintype "power_in"))
      (node (ref "NEO36") (pin "1-VDD") (pinfunction "VDD_1-VDD") (pintype "power_in"))
      (node (ref "NEO37") (pin "1-VDD") (pinfunction "VDD_1-VDD") (pintype "power_in"))
      (node (ref "NEO38") (pin "1-VDD") (pinfunction "VDD_1-VDD") (pintype "power_in"))
      (node (ref "NEO39") (pin "1-VDD") (pinfunction "VDD_1-VDD") (pintype "power_in"))
      (node (ref "NEO4") (pin "1-VDD") (pinfunction "VDD_1-VDD") (pintype "power_in"))
      (node (ref "NEO40") (pin "1-VDD") (pinfunction "VDD_1-VDD") (pintype "power_in"))
      (node (ref "NEO5") (pin "1-VDD") (pinfunction "VDD_1-VDD") (pintype "power_in"))
      (node (ref "NEO6") (pin "1-VDD") (pinfunction "VDD_1-VDD") (pintype "power_in"))
      (node (ref "NEO7") (pin "1-VDD") (pinfunction "VDD_1-VDD") (pintype "power_in"))
      (node (ref "NEO8") (pin "1-VDD") (pinfunction "VDD_1-VDD") (pintype "power_in"))
      (node (ref "NEO9") (pin "1-VDD") (pinfunction "VDD_1-VDD") (pintype "power_in"))
      (node (ref "NEOP") (pin "1") (pinfunction "1_1") (pintype "passive"))
      (node (ref "U$3") (pin "VIN") (pinfunction "VIN_VIN") (pintype "power_in"))
      (node (ref "U$6") (pin "VOUT") (pinfunction "VOUT_VOUT") (pintype "bidirectional"))
    )
    (net (code "31") (name "GND") (class "Default")
      (node (ref "5V_TEST") (pin "2") (pinfunction "2_2") (pintype "passive"))
      (node (ref "BAT_TEST") (pin "2") (pinfunction "2_2") (pintype "passive"))
      (node (ref "C1") (pin "2") (pinfunction "2_2") (pintype "passive"))
      (node (ref "C10") (pin "-") (pinfunction "-_-") (pintype "passive"))
      (node (ref "C13") (pin "2") (pinfunction "2_2") (pintype "passive"))
      (node (ref "C14") (pin "-") (pinfunction "-_-") (pintype "passive"))
      (node (ref "C15") (pin "2") (pinfunction "2_2") (pintype "passive"))
      (node (ref "C2") (pin "2") (pinfunction "2_2") (pintype "passive"))
      (node (ref "C21") (pin "2") (pinfunction "2_2") (pintype "passive"))
      (node (ref "C3") (pin "2") (pinfunction "2_2") (pintype "passive"))
      (node (ref "C4") (pin "2") (pinfunction "2_2") (pintype "passive"))
      (node (ref "C5") (pin "-") (pinfunction "-_-") (pintype "passive"))
      (node (ref "I2C0") (pin "2") (pinfunction "2_2") (pintype "passive"))
      (node (ref "I2C1") (pin "2") (pinfunction "2_2") (pintype "passive"))
      (node (ref "MEMS_R") (pin "SEL") (pinfunction "SEL_SEL") (pintype "bidirectional"))
      (node (ref "MK_REAR") (pin "2") (pinfunction "SELECT_2") (pintype "input"))
      (node (ref "NC1") (pin "2") (pinfunction "2_2") (pintype "passive"))
      (node (ref "NC10") (pin "2") (pinfunction "2_2") (pintype "passive"))
      (node (ref "NC11") (pin "2") (pinfunction "2_2") (pintype "passive"))
      (node (ref "NC12") (pin "2") (pinfunction "2_2") (pintype "passive"))
      (node (ref "NC13") (pin "2") (pinfunction "2_2") (pintype "passive"))
      (node (ref "NC14") (pin "2") (pinfunction "2_2") (pintype "passive"))
      (node (ref "NC15") (pin "2") (pinfunction "2_2") (pintype "passive"))
      (node (ref "NC16") (pin "2") (pinfunction "2_2") (pintype "passive"))
      (node (ref "NC17") (pin "2") (pinfunction "2_2") (pintype "passive"))
      (node (ref "NC18") (pin "2") (pinfunction "2_2") (pintype "passive"))
      (node (ref "NC19") (pin "2") (pinfunction "2_2") (pintype "passive"))
      (node (ref "NC2") (pin "2") (pinfunction "2_2") (pintype "passive"))
      (node (ref "NC20") (pin "2") (pinfunction "2_2") (pintype "passive"))
      (node (ref "NC21") (pin "2") (pinfunction "2_2") (pintype "passive"))
      (node (ref "NC22") (pin "2") (pinfunction "2_2") (pintype "passive"))
      (node (ref "NC23") (pin "2") (pinfunction "2_2") (pintype "passive"))
      (node (ref "NC24") (pin "2") (pinfunction "2_2") (pintype "passive"))
      (node (ref "NC25") (pin "2") (pinfunction "2_2") (pintype "passive"))
      (node (ref "NC26") (pin "2") (pinfunction "2_2") (pintype "passive"))
      (node (ref "NC27") (pin "2") (pinfunction "2_2") (pintype "passive"))
      (node (ref "NC28") (pin "2") (pinfunction "2_2") (pintype "passive"))
      (node (ref "NC29") (pin "2") (pinfunction "2_2") (pintype "passive"))
      (node (ref "NC3") (pin "2") (pinfunction "2_2") (pintype "passive"))
      (node (ref "NC30") (pin "2") (pinfunction "2_2") (pintype "passive"))
      (node (ref "NC31") (pin "2") (pinfunction "2_2") (pintype "passive"))
      (node (ref "NC32") (pin "2") (pinfunction "2_2") (pintype "passive"))
      (node (ref "NC33") (pin "2") (pinfunction "2_2") (pintype "passive"))
      (node (ref "NC34") (pin "2") (pinfunction "2_2") (pintype "passive"))
      (node (ref "NC35") (pin "2") (pinfunction "2_2") (pintype "passive"))
      (node (ref "NC36") (pin "2") (pinfunction "2_2") (pintype "passive"))
      (node (ref "NC37") (pin "2") (pinfunction "2_2") (pintype "passive"))
      (node (ref "NC38") (pin "2") (pinfunction "2_2") (pintype "passive"))
      (node (ref "NC39") (pin "2") (pinfunction "2_2") (pintype "passive"))
      (node (ref "NC4") (pin "2") (pinfunction "2_2") (pintype "passive"))
      (node (ref "NC40") (pin "2") (pinfunction "2_2") (pintype "passive"))
      (node (ref "NC5") (pin "2") (pinfunction "2_2") (pintype "passive"))
      (node (ref "NC6") (pin "2") (pinfunction "2_2") (pintype "passive"))
      (node (ref "NC7") (pin "2") (pinfunction "2_2") (pintype "passive"))
      (node (ref "NC8") (pin "2") (pinfunction "2_2") (pintype "passive"))
      (node (ref "NC9") (pin "2") (pinfunction "2_2") (pintype "passive"))
      (node (ref "NEO1") (pin "3-GND") (pinfunction "GND_3-GND") (pintype "power_in"))
      (node (ref "NEO10") (pin "3-GND") (pinfunction "GND_3-GND") (pintype "power_in"))
      (node (ref "NEO11") (pin "3-GND") (pinfunction "GND_3-GND") (pintype "power_in"))
      (node (ref "NEO12") (pin "3-GND") (pinfunction "GND_3-GND") (pintype "power_in"))
      (node (ref "NEO13") (pin "3-GND") (pinfunction "GND_3-GND") (pintype "power_in"))
      (node (ref "NEO14") (pin "3-GND") (pinfunction "GND_3-GND") (pintype "power_in"))
      (node (ref "NEO15") (pin "3-GND") (pinfunction "GND_3-GND") (pintype "power_in"))
      (node (ref "NEO16") (pin "3-GND") (pinfunction "GND_3-GND") (pintype "power_in"))
      (node (ref "NEO17") (pin "3-GND") (pinfunction "GND_3-GND") (pintype "power_in"))
      (node (ref "NEO18") (pin "3-GND") (pinfunction "GND_3-GND") (pintype "power_in"))
      (node (ref "NEO19") (pin "3-GND") (pinfunction "GND_3-GND") (pintype "power_in"))
      (node (ref "NEO2") (pin "3-GND") (pinfunction "GND_3-GND") (pintype "power_in"))
      (node (ref "NEO20") (pin "3-GND") (pinfunction "GND_3-GND") (pintype "power_in"))
      (node (ref "NEO21") (pin "3-GND") (pinfunction "GND_3-GND") (pintype "power_in"))
      (node (ref "NEO22") (pin "3-GND") (pinfunction "GND_3-GND") (pintype "power_in"))
      (node (ref "NEO23") (pin "3-GND") (pinfunction "GND_3-GND") (pintype "power_in"))
      (node (ref "NEO24") (pin "3-GND") (pinfunction "GND_3-GND") (pintype "power_in"))
      (node (ref "NEO25") (pin "3-GND") (pinfunction "GND_3-GND") (pintype "power_in"))
      (node (ref "NEO26") (pin "3-GND") (pinfunction "GND_3-GND") (pintype "power_in"))
      (node (ref "NEO27") (pin "3-GND") (pinfunction "GND_3-GND") (pintype "power_in"))
      (node (ref "NEO28") (pin "3-GND") (pinfunction "GND_3-GND") (pintype "power_in"))
      (node (ref "NEO29") (pin "3-GND") (pinfunction "GND_3-GND") (pintype "power_in"))
      (node (ref "NEO3") (pin "3-GND") (pinfunction "GND_3-GND") (pintype "power_in"))
      (node (ref "NEO30") (pin "3-GND") (pinfunction "GND_3-GND") (pintype "power_in"))
      (node (ref "NEO31") (pin "3-GND") (pinfunction "GND_3-GND") (pintype "power_in"))
      (node (ref "NEO32") (pin "3-GND") (pinfunction "GND_3-GND") (pintype "power_in"))
      (node (ref "NEO33") (pin "3-GND") (pinfunction "GND_3-GND") (pintype "power_in"))
      (node (ref "NEO34") (pin "3-GND") (pinfunction "GND_3-GND") (pintype "power_in"))
      (node (ref "NEO35") (pin "3-GND") (pinfunction "GND_3-GND") (pintype "power_in"))
      (node (ref "NEO36") (pin "3-GND") (pinfunction "GND_3-GND") (pintype "power_in"))
      (node (ref "NEO37") (pin "3-GND") (pinfunction "GND_3-GND") (pintype "power_in"))
      (node (ref "NEO38") (pin "3-GND") (pinfunction "GND_3-GND") (pintype "power_in"))
      (node (ref "NEO39") (pin "3-GND") (pinfunction "GND_3-GND") (pintype "power_in"))
      (node (ref "NEO4") (pin "3-GND") (pinfunction "GND_3-GND") (pintype "power_in"))
      (node (ref "NEO40") (pin "3-GND") (pinfunction "GND_3-GND") (pintype "power_in"))
      (node (ref "NEO5") (pin "3-GND") (pinfunction "GND_3-GND") (pintype "power_in"))
      (node (ref "NEO6") (pin "3-GND") (pinfunction "GND_3-GND") (pintype "power_in"))
      (node (ref "NEO7") (pin "3-GND") (pinfunction "GND_3-GND") (pintype "power_in"))
      (node (ref "NEO8") (pin "3-GND") (pinfunction "GND_3-GND") (pintype "power_in"))
      (node (ref "NEO9") (pin "3-GND") (pinfunction "GND_3-GND") (pintype "power_in"))
      (node (ref "NEOP") (pin "3") (pinfunction "3_3") (pintype "passive"))
      (node (ref "ON/OFF") (pin "2") (pinfunction "2_2") (pintype "passive"))
      (node (ref "S1") (pin "1") (pinfunction "1_1") (pintype "passive"))
      (node (ref "S1") (pin "10") (pinfunction "10_10") (pintype "passive"))
      (node (ref "S1") (pin "2") (pinfunction "2_2") (pintype "passive"))
      (node (ref "S1") (pin "3") (pinfunction "3_3") (pintype "passive"))
      (node (ref "S1") (pin "4") (pinfunction "4_4") (pintype "passive"))
      (node (ref "S1") (pin "5") (pinfunction "5_5") (pintype "passive"))
      (node (ref "S1") (pin "6") (pinfunction "6_6") (pintype "passive"))
      (node (ref "S1") (pin "7") (pinfunction "7_7") (pintype "passive"))
      (node (ref "S1") (pin "8") (pinfunction "8_8") (pintype "passive"))
      (node (ref "S1") (pin "9") (pinfunction "9_9") (pintype "passive"))
      (node (ref "U$1") (pin "A0") (pinfunction "A0_A0") (pintype "bidirectional"))
      (node (ref "U$1") (pin "A1") (pinfunction "A1_A1") (pintype "bidirectional"))
      (node (ref "U$1") (pin "GND") (pinfunction "GND_GND") (pintype "bidirectional"))
      (node (ref "U$2") (pin "-2") (pinfunction "-2_-2") (pintype "bidirectional"))
      (node (ref "U$3") (pin "GND") (pinfunction "GND_GND") (pintype "power_in"))
      (node (ref "U$6") (pin "GND") (pinfunction "GND_GND") (pintype "bidirectional"))
      (node (ref "VEML_B") (pin "3") (pinfunction "GND_3") (pintype "bidirectional"))
      (node (ref "VEML_F") (pin "3") (pinfunction "GND_3") (pintype "bidirectional"))
    )
    (net (code "32") (name "Net-(MK_FRONT-BCLK)") (class "Default")
      (node (ref "MK_FRONT") (pin "4") (pinfunction "BCLK_4") (pintype "input"))
      (node (ref "MK_REAR") (pin "4") (pinfunction "BCLK_4") (pintype "input"))
      (node (ref "R11") (pin "1") (pinfunction "1_1") (pintype "passive"))
    )
    (net (code "33") (name "Net-(MK_FRONT-DATA_OUT)") (class "Default")
      (node (ref "MK_FRONT") (pin "6") (pinfunction "DATA_OUT_6") (pintype "output"))
      (node (ref "R12") (pin "1") (pinfunction "1_1") (pintype "passive"))
    )
    (net (code "34") (name "Net-(MK_FRONT-WS)") (class "Default")
      (node (ref "MK_FRONT") (pin "1") (pinfunction "WS_1") (pintype "input"))
      (node (ref "MK_REAR") (pin "1") (pinfunction "WS_1") (pintype "input"))
      (node (ref "R10") (pin "1") (pinfunction "1_1") (pintype "passive"))
    )
    (net (code "35") (name "Net-(MK_REAR-DATA_OUT)") (class "Default")
      (node (ref "MK_REAR") (pin "6") (pinfunction "DATA_OUT_6") (pintype "output"))
      (node (ref "R15") (pin "1") (pinfunction "1_1") (pintype "passive"))
    )
    (net (code "36") (name "Net-(NEO1-DI)") (class "Default")
      (node (ref "NEO1") (pin "4-DIN") (pinfunction "DI_4-DIN") (pintype "input"))
      (node (ref "NEOP") (pin "2") (pinfunction "2_2") (pintype "passive"))
      (node (ref "R13") (pin "1") (pinfunction "1_1") (pintype "passive"))
    )
    (net (code "37") (name "Net-(NEO1-DO)") (class "Default")
      (node (ref "NEO1") (pin "2-DOUT") (pinfunction "DO_2-DOUT") (pintype "output"))
      (node (ref "NEO2") (pin "4-DIN") (pinfunction "DI_4-DIN") (pintype "input"))
    )
    (net (code "38") (name "Net-(NEO2-DO)") (class "Default")
      (node (ref "NEO2") (pin "2-DOUT") (pinfunction "DO_2-DOUT") (pintype "output"))
      (node (ref "NEO3") (pin "4-DIN") (pinfunction "DI_4-DIN") (pintype "input"))
    )
    (net (code "39") (name "Net-(NEO3-DO)") (class "Default")
      (node (ref "NEO3") (pin "2-DOUT") (pinfunction "DO_2-DOUT") (pintype "output"))
      (node (ref "NEO4") (pin "4-DIN") (pinfunction "DI_4-DIN") (pintype "input"))
    )
    (net (code "40") (name "Net-(NEO4-DO)") (class "Default")
      (node (ref "NEO4") (pin "2-DOUT") (pinfunction "DO_2-DOUT") (pintype "output"))
      (node (ref "NEO5") (pin "4-DIN") (pinfunction "DI_4-DIN") (pintype "input"))
    )
    (net (code "41") (name "Net-(NEO5-DO)") (class "Default")
      (node (ref "NEO5") (pin "2-DOUT") (pinfunction "DO_2-DOUT") (pintype "output"))
      (node (ref "NEO6") (pin "4-DIN") (pinfunction "DI_4-DIN") (pintype "input"))
    )
    (net (code "42") (name "Net-(NEO6-DO)") (class "Default")
      (node (ref "NEO6") (pin "2-DOUT") (pinfunction "DO_2-DOUT") (pintype "output"))
      (node (ref "NEO7") (pin "4-DIN") (pinfunction "DI_4-DIN") (pintype "input"))
    )
    (net (code "43") (name "Net-(NEO7-DO)") (class "Default")
      (node (ref "NEO7") (pin "2-DOUT") (pinfunction "DO_2-DOUT") (pintype "output"))
      (node (ref "NEO8") (pin "4-DIN") (pinfunction "DI_4-DIN") (pintype "input"))
    )
    (net (code "44") (name "Net-(NEO8-DO)") (class "Default")
      (node (ref "NEO8") (pin "2-DOUT") (pinfunction "DO_2-DOUT") (pintype "output"))
      (node (ref "NEO9") (pin "4-DIN") (pinfunction "DI_4-DIN") (pintype "input"))
    )
    (net (code "45") (name "Net-(NEO10-DI)") (class "Default")
      (node (ref "NEO10") (pin "4-DIN") (pinfunction "DI_4-DIN") (pintype "input"))
      (node (ref "NEO9") (pin "2-DOUT") (pinfunction "DO_2-DOUT") (pintype "output"))
    )
    (net (code "46") (name "Net-(NEO11-DI)") (class "Default")
      (node (ref "NEO11") (pin "4-DIN") (pinfunction "DI_4-DIN") (pintype "input"))
      (node (ref "NEO16") (pin "2-DOUT") (pinfunction "DO_2-DOUT") (pintype "output"))
    )
    (net (code "47") (name "Net-(NEO11-DO)") (class "Default")
      (node (ref "NEO11") (pin "2-DOUT") (pinfunction "DO_2-DOUT") (pintype "output"))
      (node (ref "NEO12") (pin "4-DIN") (pinfunction "DI_4-DIN") (pintype "input"))
    )
    (net (code "48") (name "Net-(NEO12-DO)") (class "Default")
      (node (ref "NEO12") (pin "2-DOUT") (pinfunction "DO_2-DOUT") (pintype "output"))
      (node (ref "NEO13") (pin "4-DIN") (pinfunction "DI_4-DIN") (pintype "input"))
    )
    (net (code "49") (name "Net-(NEO13-DO)") (class "Default")
      (node (ref "NEO13") (pin "2-DOUT") (pinfunction "DO_2-DOUT") (pintype "output"))
      (node (ref "NEO17") (pin "4-DIN") (pinfunction "DI_4-DIN") (pintype "input"))
    )
    (net (code "50") (name "Net-(NEO14-DO)") (class "Default")
      (node (ref "NEO14") (pin "2-DOUT") (pinfunction "DO_2-DOUT") (pintype "output"))
      (node (ref "NEO15") (pin "4-DIN") (pinfunction "DI_4-DIN") (pintype "input"))
    )
    (net (code "51") (name "Net-(NEO15-DO)") (class "Default")
      (node (ref "NEO15") (pin "2-DOUT") (pinfunction "DO_2-DOUT") (pintype "output"))
      (node (ref "NEO16") (pin "4-DIN") (pinfunction "DI_4-DIN") (pintype "input"))
    )
    (net (code "52") (name "Net-(NEO17-DO)") (class "Default")
      (node (ref "NEO17") (pin "2-DOUT") (pinfunction "DO_2-DOUT") (pintype "output"))
      (node (ref "NEO18") (pin "4-DIN") (pinfunction "DI_4-DIN") (pintype "input"))
    )
    (net (code "53") (name "Net-(NEO18-DO)") (class "Default")
      (node (ref "NEO18") (pin "2-DOUT") (pinfunction "DO_2-DOUT") (pintype "output"))
      (node (ref "NEO19") (pin "4-DIN") (pinfunction "DI_4-DIN") (pintype "input"))
    )
    (net (code "54") (name "Net-(NEO19-DO)") (class "Default")
      (node (ref "NEO19") (pin "2-DOUT") (pinfunction "DO_2-DOUT") (pintype "output"))
      (node (ref "NEO20") (pin "4-DIN") (pinfunction "DI_4-DIN") (pintype "input"))
    )
    (net (code "55") (name "Net-(NEO21-DI)") (class "Default")
      (node (ref "NEO21") (pin "4-DIN") (pinfunction "DI_4-DIN") (pintype "input"))
      (node (ref "NEO26") (pin "2-DOUT") (pinfunction "DO_2-DOUT") (pintype "output"))
    )
    (net (code "56") (name "Net-(NEO21-DO)") (class "Default")
      (node (ref "NEO21") (pin "2-DOUT") (pinfunction "DO_2-DOUT") (pintype "output"))
      (node (ref "NEO22") (pin "4-DIN") (pinfunction "DI_4-DIN") (pintype "input"))
    )
    (net (code "57") (name "Net-(NEO22-DO)") (class "Default")
      (node (ref "NEO22") (pin "2-DOUT") (pinfunction "DO_2-DOUT") (pintype "output"))
      (node (ref "NEO23") (pin "4-DIN") (pinfunction "DI_4-DIN") (pintype "input"))
    )
    (net (code "58") (name "Net-(NEO23-DO)") (class "Default")
      (node (ref "NEO23") (pin "2-DOUT") (pinfunction "DO_2-DOUT") (pintype "output"))
      (node (ref "NEO27") (pin "4-DIN") (pinfunction "DI_4-DIN") (pintype "input"))
    )
    (net (code "59") (name "Net-(NEO24-DO)") (class "Default")
      (node (ref "NEO24") (pin "2-DOUT") (pinfunction "DO_2-DOUT") (pintype "output"))
      (node (ref "NEO25") (pin "4-DIN") (pinfunction "DI_4-DIN") (pintype "input"))
    )
    (net (code "60") (name "Net-(NEO25-DO)") (class "Default")
      (node (ref "NEO25") (pin "2-DOUT") (pinfunction "DO_2-DOUT") (pintype "output"))
      (node (ref "NEO26") (pin "4-DIN") (pinfunction "DI_4-DIN") (pintype "input"))
    )
    (net (code "61") (name "Net-(NEO27-DO)") (class "Default")
      (node (ref "NEO27") (pin "2-DOUT") (pinfunction "DO_2-DOUT") (pintype "output"))
      (node (ref "NEO28") (pin "4-DIN") (pinfunction "DI_4-DIN") (pintype "input"))
    )
    (net (code "62") (name "Net-(NEO28-DO)") (class "Default")
      (node (ref "NEO28") (pin "2-DOUT") (pinfunction "DO_2-DOUT") (pintype "output"))
      (node (ref "NEO29") (pin "4-DIN") (pinfunction "DI_4-DIN") (pintype "input"))
    )
    (net (code "63") (name "Net-(NEO29-DO)") (class "Default")
      (node (ref "NEO29") (pin "2-DOUT") (pinfunction "DO_2-DOUT") (pintype "output"))
      (node (ref "NEO30") (pin "4-DIN") (pinfunction "DI_4-DIN") (pintype "input"))
    )
    (net (code "64") (name "Net-(NEO31-DI)") (class "Default")
      (node (ref "NEO31") (pin "4-DIN") (pinfunction "DI_4-DIN") (pintype "input"))
      (node (ref "NEO36") (pin "2-DOUT") (pinfunction "DO_2-DOUT") (pintype "output"))
    )
    (net (code "65") (name "Net-(NEO31-DO)") (class "Default")
      (node (ref "NEO31") (pin "2-DOUT") (pinfunction "DO_2-DOUT") (pintype "output"))
      (node (ref "NEO32") (pin "4-DIN") (pinfunction "DI_4-DIN") (pintype "input"))
    )
    (net (code "66") (name "Net-(NEO32-DO)") (class "Default")
      (node (ref "NEO32") (pin "2-DOUT") (pinfunction "DO_2-DOUT") (pintype "output"))
      (node (ref "NEO33") (pin "4-DIN") (pinfunction "DI_4-DIN") (pintype "input"))
    )
    (net (code "67") (name "Net-(NEO33-DO)") (class "Default")
      (node (ref "NEO33") (pin "2-DOUT") (pinfunction "DO_2-DOUT") (pintype "output"))
      (node (ref "NEO37") (pin "4-DIN") (pinfunction "DI_4-DIN") (pintype "input"))
    )
    (net (code "68") (name "Net-(NEO34-DO)") (class "Default")
      (node (ref "NEO34") (pin "2-DOUT") (pinfunction "DO_2-DOUT") (pintype "output"))
      (node (ref "NEO35") (pin "4-DIN") (pinfunction "DI_4-DIN") (pintype "input"))
    )
    (net (code "69") (name "Net-(NEO35-DO)") (class "Default")
      (node (ref "NEO35") (pin "2-DOUT") (pinfunction "DO_2-DOUT") (pintype "output"))
      (node (ref "NEO36") (pin "4-DIN") (pinfunction "DI_4-DIN") (pintype "input"))
    )
    (net (code "70") (name "Net-(NEO37-DO)") (class "Default")
      (node (ref "NEO37") (pin "2-DOUT") (pinfunction "DO_2-DOUT") (pintype "output"))
      (node (ref "NEO38") (pin "4-DIN") (pinfunction "DI_4-DIN") (pintype "input"))
    )
    (net (code "71") (name "Net-(NEO38-DO)") (class "Default")
      (node (ref "NEO38") (pin "2-DOUT") (pinfunction "DO_2-DOUT") (pintype "output"))
      (node (ref "NEO39") (pin "4-DIN") (pinfunction "DI_4-DIN") (pintype "input"))
    )
    (net (code "72") (name "Net-(NEO39-DO)") (class "Default")
      (node (ref "NEO39") (pin "2-DOUT") (pinfunction "DO_2-DOUT") (pintype "output"))
      (node (ref "NEO40") (pin "4-DIN") (pinfunction "DI_4-DIN") (pintype "input"))
    )
    (net (code "73") (name "Net-(R23-Pad1)") (class "Default")
      (node (ref "R23") (pin "1") (pinfunction "1_1") (pintype "passive"))
      (node (ref "S1") (pin "20") (pinfunction "20_20") (pintype "passive"))
    )
    (net (code "74") (name "Net-(R24-Pad1)") (class "Default")
      (node (ref "R24") (pin "1") (pinfunction "1_1") (pintype "passive"))
      (node (ref "S1") (pin "11") (pinfunction "11_11") (pintype "passive"))
    )
    (net (code "75") (name "Net-(U$2-Pad+2)") (class "Default")
      (node (ref "U$2") (pin "+2") (pinfunction "+2_+2") (pintype "bidirectional"))
      (node (ref "U$2") (pin "-1") (pinfunction "-1_-1") (pintype "bidirectional"))
    )
    (net (code "76") (name "Net-(VEML_B-VDD)") (class "Default")
      (node (ref "C2") (pin "1") (pinfunction "1_1") (pintype "passive"))
      (node (ref "C3") (pin "1") (pinfunction "1_1") (pintype "passive"))
      (node (ref "R4") (pin "1") (pinfunction "1_1") (pintype "passive"))
      (node (ref "VEML_B") (pin "2") (pinfunction "VDD_2") (pintype "bidirectional"))
    )
    (net (code "77") (name "Net-(VEML_F-VDD)") (class "Default")
      (node (ref "C1") (pin "1") (pinfunction "1_1") (pintype "passive"))
      (node (ref "C4") (pin "1") (pinfunction "1_1") (pintype "passive"))
      (node (ref "R3") (pin "1") (pinfunction "1_1") (pintype "passive"))
      (node (ref "VEML_F") (pin "2") (pinfunction "VDD_2") (pintype "bidirectional"))
    )
    (net (code "78") (name "unconnected-(NEO40-DO-Pad2-DOUT)") (class "Default")
      (node (ref "NEO40") (pin "2-DOUT") (pinfunction "DO_2-DOUT") (pintype "output"))
    )
    (net (code "79") (name "unconnected-(R16-Pad2)") (class "Default")
      (node (ref "R16") (pin "2") (pinfunction "2_2") (pintype "passive"))
    )
    (net (code "80") (name "unconnected-(R17-Pad2)") (class "Default")
      (node (ref "R17") (pin "2") (pinfunction "2_2") (pintype "passive"))
    )
    (net (code "81") (name "unconnected-(R18-Pad2)") (class "Default")
      (node (ref "R18") (pin "2") (pinfunction "2_2") (pintype "passive"))
    )
    (net (code "82") (name "unconnected-(R19-Pad2)") (class "Default")
      (node (ref "R19") (pin "2") (pinfunction "2_2") (pintype "passive"))
    )
    (net (code "83") (name "unconnected-(R20-Pad2)") (class "Default")
      (node (ref "R20") (pin "2") (pinfunction "2_2") (pintype "passive"))
    )
    (net (code "84") (name "unconnected-(R21-Pad2)") (class "Default")
      (node (ref "R21") (pin "2") (pinfunction "2_2") (pintype "passive"))
    )
    (net (code "85") (name "unconnected-(U$1-PadINT)") (class "Default")
      (node (ref "U$1") (pin "INT") (pinfunction "INT_INT") (pintype "bidirectional"))
    )
    (net (code "86") (name "unconnected-(U$1-PadINT0)") (class "Default")
      (node (ref "U$1") (pin "INT0") (pinfunction "INT0_INT0") (pintype "bidirectional"))
    )
    (net (code "87") (name "unconnected-(U$1-PadINT1)") (class "Default")
      (node (ref "U$1") (pin "INT1") (pinfunction "INT1_INT1") (pintype "bidirectional"))
    )
    (net (code "88") (name "unconnected-(U$3-0{slash}RX1{slash}T-Pad0)") (class "Default")
      (node (ref "U$3") (pin "0") (pinfunction "0/RX1/T_0") (pintype "bidirectional"))
    )
    (net (code "89") (name "unconnected-(U$3-1{slash}TX1{slash}T-Pad1)") (class "Default")
      (node (ref "U$3") (pin "1") (pinfunction "1/TX1/T_1") (pintype "bidirectional"))
    )
    (net (code "90") (name "unconnected-(U$3-3{slash}CAN-TX{slash}PWM-Pad3)") (class "Default")
      (node (ref "U$3") (pin "3") (pinfunction "3/CAN-TX/PWM_3") (pintype "bidirectional"))
    )
    (net (code "91") (name "unconnected-(U$3-4{slash}CAN-RX{slash}PWM-Pad4)") (class "Default")
      (node (ref "U$3") (pin "4") (pinfunction "4/CAN-RX/PWM_4") (pintype "bidirectional"))
    )
    (net (code "92") (name "unconnected-(U$3-7{slash}RX3-Pad7)") (class "Default")
      (node (ref "U$3") (pin "7") (pinfunction "7/RX3_7") (pintype "bidirectional"))
    )
    (net (code "93") (name "unconnected-(U$3-8{slash}TX3-Pad8)") (class "Default")
      (node (ref "U$3") (pin "8") (pinfunction "8/TX3_8") (pintype "bidirectional"))
    )
    (net (code "94") (name "unconnected-(U$3-10{slash}TX2{slash}PWM-Pad10)") (class "Default")
      (node (ref "U$3") (pin "10") (pinfunction "10/TX2/PWM_10") (pintype "bidirectional"))
    )
  )
)
